# sensors.net
KiCad netlist of a schematic drawn in Altium Designer
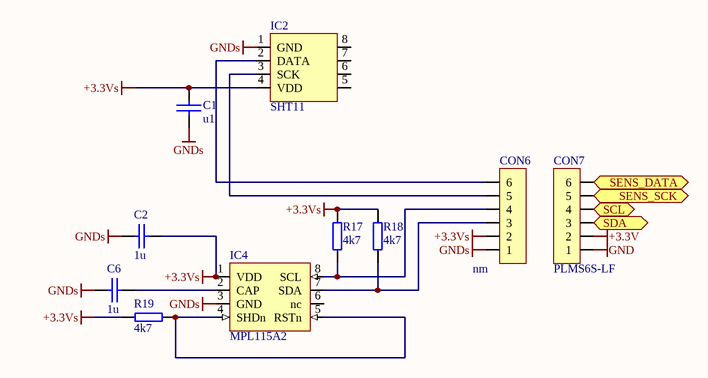
[diagram p0: sensors.SchDoc]

(export (version "E")
  (design (tool "Eeschema 10.0.6"))
  (components
    (comp (ref "C1")
      (value "u1")
      (footprint "0603")
      (description "Capacitor SMD")
      (libsource (lib "LIBRARY_SCH") (part "CAP_SMD"))
    )
    (comp (ref "C2")
      (value "1u")
      (footprint "0603")
      (description "Capacitor SMD")
      (libsource (lib "LIBRARY_SCH") (part "CAP_SMD"))
    )
    (comp (ref "C6")
      (value "1u")
      (footprint "0603")
      (description "Capacitor SMD")
      (libsource (lib "LIBRARY_SCH") (part "CAP_SMD"))
    )
    (comp (ref "CON6")
      (value "nm")
      (footprint "PLMS6R-2LF")
      (description "2mm RA goldpin")
      (libsource (lib "LIBRARY_SCH") (part "CON_6_goldpin_RA_2mm"))
    )
    (comp (ref "CON7")
      (value "PLMS6S-LF")
      (footprint "PLMS6R-2LF")
      (description "2mm RA goldpin")
      (libsource (lib "") (part "CON_6_goldpin_RA_2mm_1"))
    )
    (comp (ref "IC2")
      (value "SHT11")
      (footprint "SHT11")
      (description "temp/humidity sensor")
      (libsource (lib "*") (part "SHT11"))
    )
    (comp (ref "IC4")
      (value "MPL115A2")
      (footprint "LGA8")
      (description "Miniature I2C Digital Barometer")
      (libsource (lib "LIBRARY_SCH") (part "SENS_MPL115A2"))
    )
    (comp (ref "R17")
      (value "4k7")
      (footprint "0603")
      (description "SMD Resistor")
      (libsource (lib "LIBRARY_SCH") (part "RES_SMD"))
    )
    (comp (ref "R18")
      (value "4k7")
      (footprint "0603")
      (description "SMD Resistor")
      (libsource (lib "LIBRARY_SCH") (part "RES_SMD"))
    )
    (comp (ref "R19")
      (value "4k7")
      (footprint "0603")
      (description "SMD Resistor")
      (libsource (lib "LIBRARY_SCH") (part "RES_SMD"))
    )
  )
  (nets
    (net (code "1") (name "+3.3V") (class "Default")
      (node (ref "CON7") (pin "2") (pinfunction "2_2") (pintype "passive"))
    )
    (net (code "2") (name "+3.3Vs") (class "Default")
      (node (ref "C1") (pin "1") (pinfunction "1_1") (pintype "passive"))
      (node (ref "C2") (pin "2") (pinfunction "2_2") (pintype "passive"))
      (node (ref "CON6") (pin "2") (pinfunction "2_2") (pintype "passive"))
      (node (ref "IC2") (pin "4") (pinfunction "VDD_4") (pintype "passive"))
      (node (ref "IC4") (pin "1") (pinfunction "VDD_1") (pintype "power_in"))
      (node (ref "R17") (pin "2") (pinfunction "2_2") (pintype "passive"))
      (node (ref "R18") (pin "2") (pinfunction "2_2") (pintype "passive"))
      (node (ref "R19") (pin "2") (pinfunction "2_2") (pintype "passive"))
    )
    (net (code "3") (name "/SCL") (class "Default")
      (node (ref "CON7") (pin "4") (pinfunction "4_4") (pintype "passive"))
    )
    (net (code "4") (name "/SDA") (class "Default")
      (node (ref "CON7") (pin "3") (pinfunction "3_3") (pintype "passive"))
    )
    (net (code "5") (name "/SENS_DATA") (class "Default")
      (node (ref "CON7") (pin "6") (pinfunction "6_6") (pintype "passive"))
    )
    (net (code "6") (name "/SENS_SCK") (class "Default")
      (node (ref "CON7") (pin "5") (pinfunction "5_5") (pintype "passive"))
    )
    (net (code "7") (name "GND") (class "Default")
      (node (ref "CON7") (pin "1") (pinfunction "1_1") (pintype "passive"))
    )
    (net (code "8") (name "GNDs") (class "Default")
      (node (ref "C1") (pin "2") (pinfunction "2_2") (pintype "passive"))
      (node (ref "C2") (pin "1") (pinfunction "1_1") (pintype "passive"))
      (node (ref "C6") (pin "1") (pinfunction "1_1") (pintype "passive"))
      (node (ref "CON6") (pin "1") (pinfunction "1_1") (pintype "passive"))
      (node (ref "IC2") (pin "1") (pinfunction "GND_1") (pintype "passive"))
      (node (ref "IC4") (pin "3") (pinfunction "GND_3") (pintype "power_in"))
    )
    (net (code "9") (name "Net-(IC2-DATA)") (class "Default")
      (node (ref "CON6") (pin "6") (pinfunction "6_6") (pintype "passive"))
      (node (ref "IC2") (pin "2") (pinfunction "DATA_2") (pintype "passive"))
    )
    (net (code "10") (name "Net-(IC2-SCK)") (class "Default")
      (node (ref "CON6") (pin "5") (pinfunction "5_5") (pintype "passive"))
      (node (ref "IC2") (pin "3") (pinfunction "SCK_3") (pintype "passive"))
    )
    (net (code "11") (name "Net-(IC4-CAP)") (class "Default")
      (node (ref "C6") (pin "2") (pinfunction "2_2") (pintype "passive"))
      (node (ref "IC4") (pin "2") (pinfunction "CAP_2") (pintype "passive"))
    )
    (net (code "12") (name "Net-(IC4-RSTn)") (class "Default")
      (node (ref "IC4") (pin "4") (pinfunction "SHDn_4") (pintype "input"))
      (node (ref "IC4") (pin "5") (pinfunction "RSTn_5") (pintype "input"))
      (node (ref "R19") (pin "1") (pinfunction "1_1") (pintype "passive"))
    )
    (net (code "13") (name "Net-(IC4-SCL)") (class "Default")
      (node (ref "CON6") (pin "4") (pinfunction "4_4") (pintype "passive"))
      (node (ref "IC4") (pin "8") (pinfunction "SCL_8") (pintype "input"))
      (node (ref "R17") (pin "1") (pinfunction "1_1") (pintype "passive"))
    )
    (net (code "14") (name "Net-(IC4-SDA)") (class "Default")
      (node (ref "CON6") (pin "3") (pinfunction "3_3") (pintype "passive"))
      (node (ref "IC4") (pin "7") (pinfunction "SDA_7") (pintype "bidirectional"))
      (node (ref "R18") (pin "1") (pinfunction "1_1") (pintype "passive"))
    )
    (net (code "15") (name "unconnected-(IC2-Pad5)") (class "Default")
      (node (ref "IC2") (pin "5") (pinfunction "5_5") (pintype "passive"))
    )
    (net (code "16") (name "unconnected-(IC2-Pad6)") (class "Default")
      (node (ref "IC2") (pin "6") (pinfunction "6_6") (pintype "passive"))
    )
    (net (code "17") (name "unconnected-(IC2-Pad7)") (class "Default")
      (node (ref "IC2") (pin "7") (pinfunction "7_7") (pintype "passive"))
    )
    (net (code "18") (name "unconnected-(IC2-Pad8)") (class "Default")
      (node (ref "IC2") (pin "8") (pinfunction "8_8") (pintype "passive"))
    )
    (net (code "19") (name "unconnected-(IC4-nc-Pad6)") (class "Default")
      (node (ref "IC4") (pin "6") (pinfunction "nc_6") (pintype "passive"))
    )
  )
)
